# USB_DV_Stick_1V1_Sheet3.net
KiCad netlist of a schematic drawn in Altium Designer
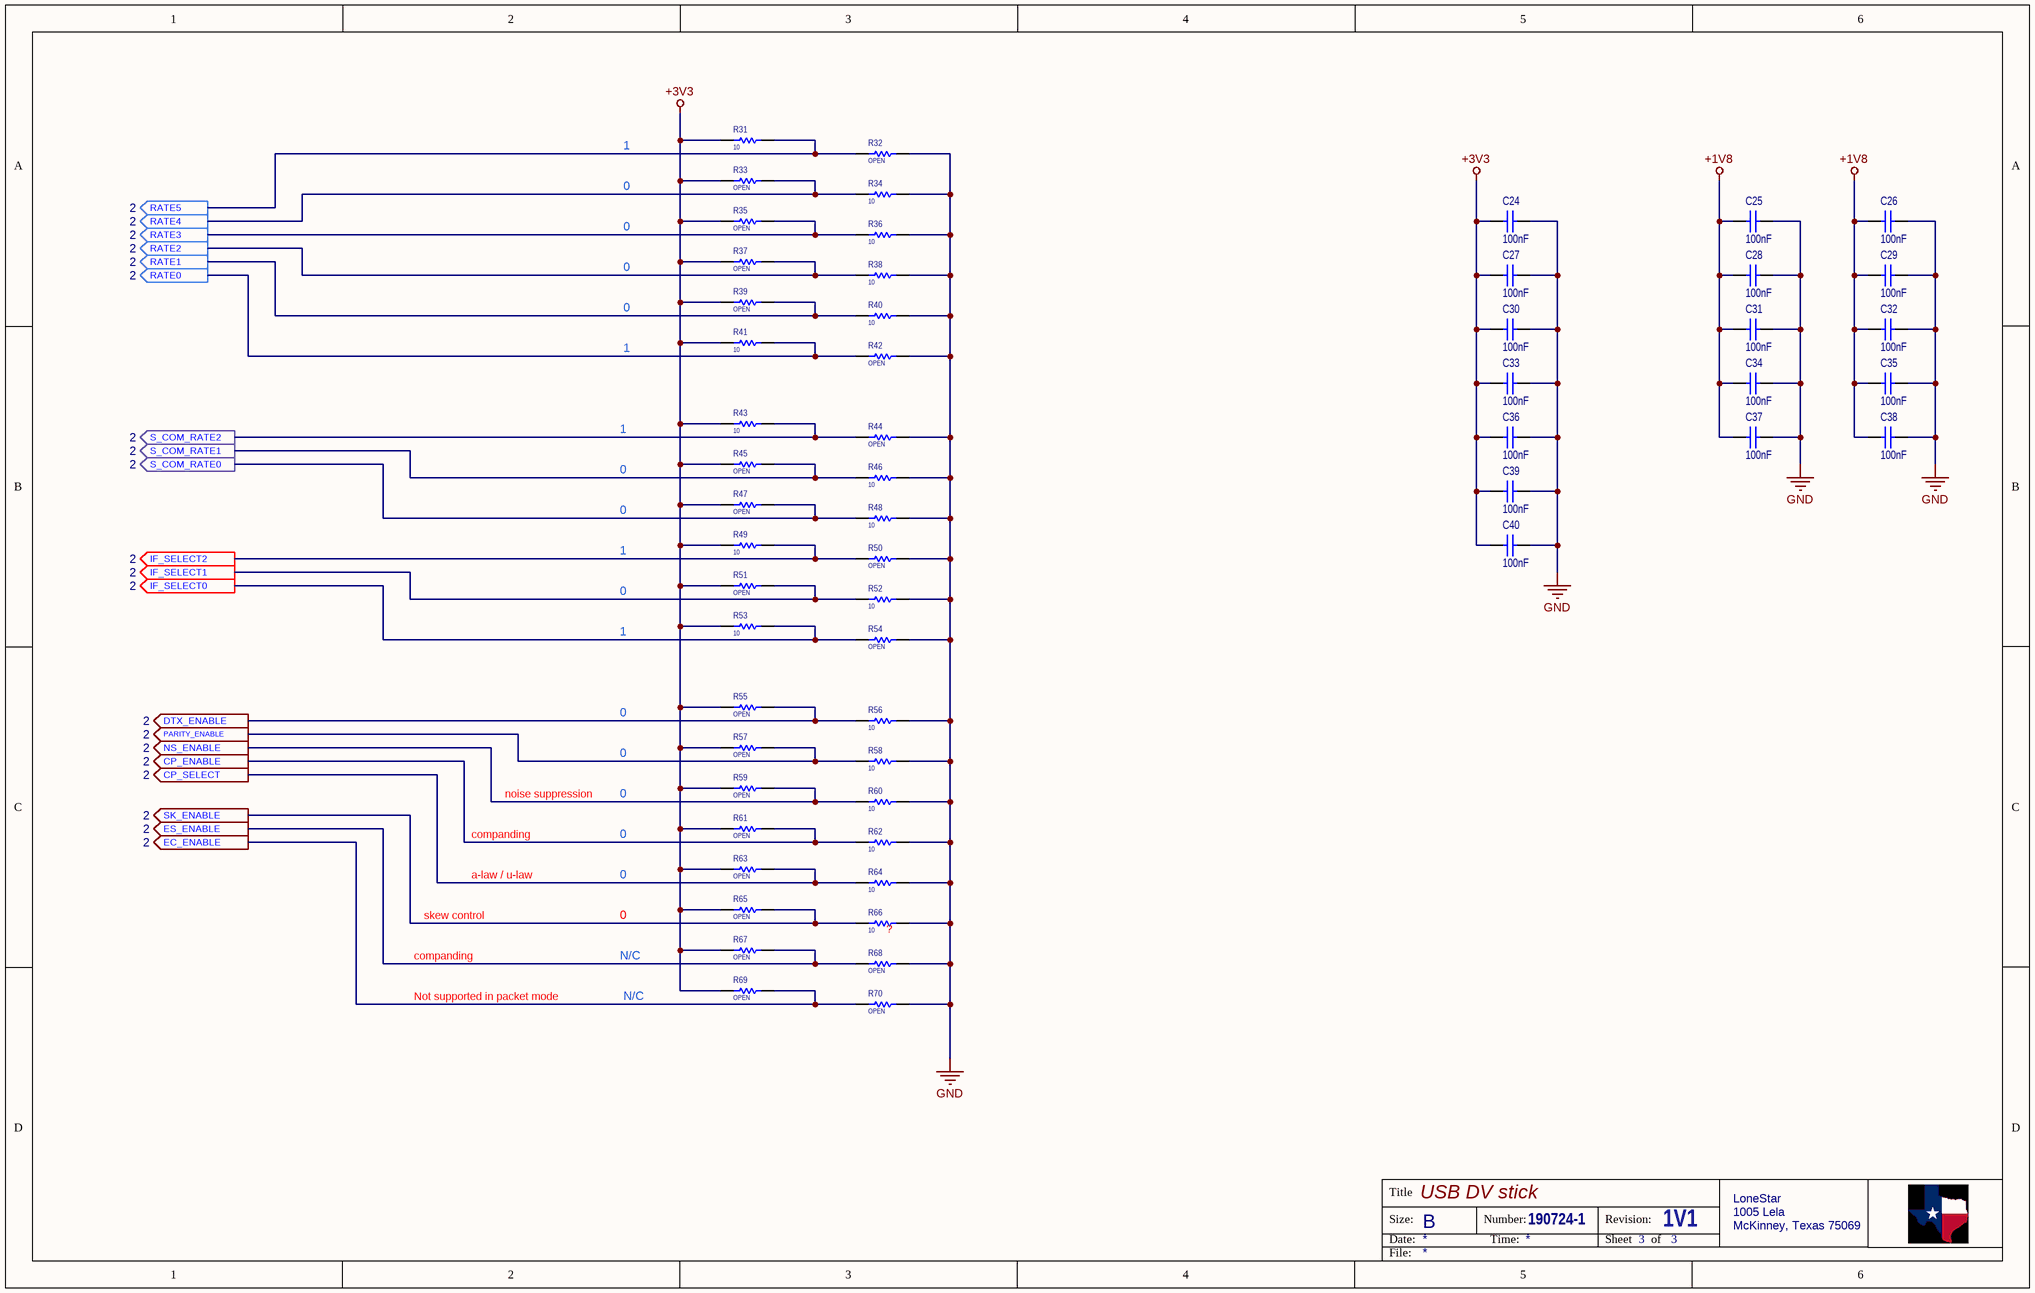
[diagram p0: USB DV Stick 1V1_Sheet3.SchDoc]

(export (version "E")
  (design (tool "Eeschema 10.0.6"))
  (components
    (comp (ref "C24")
      (value "100nF")
      (footprint "C0402")
      (description "Capacitor Surface Mount")
      (fields
        (field (name "MANUFACTURER") "Murata Electronics")
        (field (name "MANUFACTURER PART NUMBER") "GRM155R61H104KE19D")
      )
      (libsource (lib "Dave's") (part "Cap SM"))
    )
    (comp (ref "C25")
      (value "100nF")
      (footprint "C0402")
      (description "Capacitor Surface Mount")
      (fields
        (field (name "MANUFACTURER") "Murata Electronics")
        (field (name "MANUFACTURER PART NUMBER") "GRM155R61H104KE19D")
      )
      (libsource (lib "Dave's") (part "Cap SM"))
    )
    (comp (ref "C26")
      (value "100nF")
      (footprint "C0402")
      (description "Capacitor Surface Mount")
      (fields
        (field (name "MANUFACTURER") "Murata Electronics")
        (field (name "MANUFACTURER PART NUMBER") "GRM155R61H104KE19D")
      )
      (libsource (lib "Dave's") (part "Cap SM"))
    )
    (comp (ref "C27")
      (value "100nF")
      (footprint "C0402")
      (description "Capacitor Surface Mount")
      (fields
        (field (name "MANUFACTURER") "Murata Electronics")
        (field (name "MANUFACTURER PART NUMBER") "GRM155R61H104KE19D")
      )
      (libsource (lib "Dave's") (part "Cap SM"))
    )
    (comp (ref "C28")
      (value "100nF")
      (footprint "C0402")
      (description "Capacitor Surface Mount")
      (fields
        (field (name "MANUFACTURER") "Murata Electronics")
        (field (name "MANUFACTURER PART NUMBER") "GRM155R61H104KE19D")
      )
      (libsource (lib "Dave's") (part "Cap SM"))
    )
    (comp (ref "C29")
      (value "100nF")
      (footprint "C0402")
      (description "Capacitor Surface Mount")
      (fields
        (field (name "MANUFACTURER") "Murata Electronics")
        (field (name "MANUFACTURER PART NUMBER") "GRM155R61H104KE19D")
      )
      (libsource (lib "Dave's") (part "Cap SM"))
    )
    (comp (ref "C30")
      (value "100nF")
      (footprint "C0402")
      (description "Capacitor Surface Mount")
      (fields
        (field (name "MANUFACTURER") "Murata Electronics")
        (field (name "MANUFACTURER PART NUMBER") "GRM155R61H104KE19D")
      )
      (libsource (lib "Dave's") (part "Cap SM"))
    )
    (comp (ref "C31")
      (value "100nF")
      (footprint "C0402")
      (description "Capacitor Surface Mount")
      (fields
        (field (name "MANUFACTURER") "Murata Electronics")
        (field (name "MANUFACTURER PART NUMBER") "GRM155R61H104KE19D")
      )
      (libsource (lib "Dave's") (part "Cap SM"))
    )
    (comp (ref "C32")
      (value "100nF")
      (footprint "C0402")
      (description "Capacitor Surface Mount")
      (fields
        (field (name "MANUFACTURER") "Murata Electronics")
        (field (name "MANUFACTURER PART NUMBER") "GRM155R61H104KE19D")
      )
      (libsource (lib "Dave's") (part "Cap SM"))
    )
    (comp (ref "C33")
      (value "100nF")
      (footprint "C0402")
      (description "Capacitor Surface Mount")
      (fields
        (field (name "MANUFACTURER") "Murata Electronics")
        (field (name "MANUFACTURER PART NUMBER") "GRM155R61H104KE19D")
      )
      (libsource (lib "Dave's") (part "Cap SM"))
    )
    (comp (ref "C34")
      (value "100nF")
      (footprint "C0402")
      (description "Capacitor Surface Mount")
      (fields
        (field (name "MANUFACTURER") "Murata Electronics")
        (field (name "MANUFACTURER PART NUMBER") "GRM155R61H104KE19D")
      )
      (libsource (lib "Dave's") (part "Cap SM"))
    )
    (comp (ref "C35")
      (value "100nF")
      (footprint "C0402")
      (description "Capacitor Surface Mount")
      (fields
        (field (name "MANUFACTURER") "Murata Electronics")
        (field (name "MANUFACTURER PART NUMBER") "GRM155R61H104KE19D")
      )
      (libsource (lib "Dave's") (part "Cap SM"))
    )
    (comp (ref "C36")
      (value "100nF")
      (footprint "C0402")
      (description "Capacitor Surface Mount")
      (fields
        (field (name "MANUFACTURER") "Murata Electronics")
        (field (name "MANUFACTURER PART NUMBER") "GRM155R61H104KE19D")
      )
      (libsource (lib "Dave's") (part "Cap SM"))
    )
    (comp (ref "C37")
      (value "100nF")
      (footprint "C0402")
      (description "Capacitor Surface Mount")
      (fields
        (field (name "MANUFACTURER") "Murata Electronics")
        (field (name "MANUFACTURER PART NUMBER") "GRM155R61H104KE19D")
      )
      (libsource (lib "Dave's") (part "Cap SM"))
    )
    (comp (ref "C38")
      (value "100nF")
      (footprint "C0402")
      (description "Capacitor Surface Mount")
      (fields
        (field (name "MANUFACTURER") "Murata Electronics")
        (field (name "MANUFACTURER PART NUMBER") "GRM155R61H104KE19D")
      )
      (libsource (lib "Dave's") (part "Cap SM"))
    )
    (comp (ref "C39")
      (value "100nF")
      (footprint "C0402")
      (description "Capacitor Surface Mount")
      (fields
        (field (name "MANUFACTURER") "Murata Electronics")
        (field (name "MANUFACTURER PART NUMBER") "GRM155R61H104KE19D")
      )
      (libsource (lib "Dave's") (part "Cap SM"))
    )
    (comp (ref "C40")
      (value "100nF")
      (footprint "C0402")
      (description "Capacitor Surface Mount")
      (fields
        (field (name "MANUFACTURER") "Murata Electronics")
        (field (name "MANUFACTURER PART NUMBER") "GRM155R61H104KE19D")
      )
      (libsource (lib "Dave's") (part "Cap SM"))
    )
    (comp (ref "R31")
      (value "10")
      (footprint "R0603")
      (description "Resistor Surface Mount")
      (fields
        (field (name "MANUFACTURER") "Vishay / Dale")
        (field (name "MANUFACTURER PART NUMBER") "CRCW060310R0FKEAC")
      )
      (libsource (lib "Dave's") (part "RES SM"))
    )
    (comp (ref "R32")
      (value "OPEN")
      (footprint "R0603")
      (description "Resistor Surface Mount")
      (libsource (lib "Dave's") (part "RES SM"))
    )
    (comp (ref "R33")
      (value "OPEN")
      (footprint "R0603")
      (description "Resistor Surface Mount")
      (libsource (lib "Dave's") (part "RES SM"))
    )
    (comp (ref "R34")
      (value "10")
      (footprint "R0603")
      (description "Resistor Surface Mount")
      (fields
        (field (name "MANUFACTURER") "Vishay / Dale")
        (field (name "MANUFACTURER PART NUMBER") "CRCW060310R0FKEAC")
      )
      (libsource (lib "Dave's") (part "RES SM"))
    )
    (comp (ref "R35")
      (value "OPEN")
      (footprint "R0603")
      (description "Resistor Surface Mount")
      (libsource (lib "Dave's") (part "RES SM"))
    )
    (comp (ref "R36")
      (value "10")
      (footprint "R0603")
      (description "Resistor Surface Mount")
      (fields
        (field (name "MANUFACTURER") "Vishay / Dale")
        (field (name "MANUFACTURER PART NUMBER") "CRCW060310R0FKEAC")
      )
      (libsource (lib "Dave's") (part "RES SM"))
    )
    (comp (ref "R37")
      (value "OPEN")
      (footprint "R0603")
      (description "Resistor Surface Mount")
      (libsource (lib "Dave's") (part "RES SM"))
    )
    (comp (ref "R38")
      (value "10")
      (footprint "R0603")
      (description "Resistor Surface Mount")
      (fields
        (field (name "MANUFACTURER") "Vishay / Dale")
        (field (name "MANUFACTURER PART NUMBER") "CRCW060310R0FKEAC")
      )
      (libsource (lib "Dave's") (part "RES SM"))
    )
    (comp (ref "R39")
      (value "OPEN")
      (footprint "R0603")
      (description "Resistor Surface Mount")
      (libsource (lib "Dave's") (part "RES SM"))
    )
    (comp (ref "R40")
      (value "10")
      (footprint "R0603")
      (description "Resistor Surface Mount")
      (fields
        (field (name "MANUFACTURER") "Vishay / Dale")
        (field (name "MANUFACTURER PART NUMBER") "CRCW060310R0FKEAC")
      )
      (libsource (lib "Dave's") (part "RES SM"))
    )
    (comp (ref "R41")
      (value "10")
      (footprint "R0603")
      (description "Resistor Surface Mount")
      (fields
        (field (name "MANUFACTURER") "Vishay / Dale")
        (field (name "MANUFACTURER PART NUMBER") "CRCW060310R0FKEAC")
      )
      (libsource (lib "Dave's") (part "RES SM"))
    )
    (comp (ref "R42")
      (value "OPEN")
      (footprint "R0603")
      (description "Resistor Surface Mount")
      (libsource (lib "Dave's") (part "RES SM"))
    )
    (comp (ref "R43")
      (value "10")
      (footprint "R0603")
      (description "Resistor Surface Mount")
      (fields
        (field (name "MANUFACTURER") "Vishay / Dale")
        (field (name "MANUFACTURER PART NUMBER") "CRCW060310R0FKEAC")
      )
      (libsource (lib "Dave's") (part "RES SM"))
    )
    (comp (ref "R44")
      (value "OPEN")
      (footprint "R0603")
      (description "Resistor Surface Mount")
      (libsource (lib "Dave's") (part "RES SM"))
    )
    (comp (ref "R45")
      (value "OPEN")
      (footprint "R0603")
      (description "Resistor Surface Mount")
      (libsource (lib "Dave's") (part "RES SM"))
    )
    (comp (ref "R46")
      (value "10")
      (footprint "R0603")
      (description "Resistor Surface Mount")
      (fields
        (field (name "MANUFACTURER") "Vishay / Dale")
        (field (name "MANUFACTURER PART NUMBER") "CRCW060310R0FKEAC")
      )
      (libsource (lib "Dave's") (part "RES SM"))
    )
    (comp (ref "R47")
      (value "OPEN")
      (footprint "R0603")
      (description "Resistor Surface Mount")
      (libsource (lib "Dave's") (part "RES SM"))
    )
    (comp (ref "R48")
      (value "10")
      (footprint "R0603")
      (description "Resistor Surface Mount")
      (fields
        (field (name "MANUFACTURER") "Vishay / Dale")
        (field (name "MANUFACTURER PART NUMBER") "CRCW060310R0FKEAC")
      )
      (libsource (lib "Dave's") (part "RES SM"))
    )
    (comp (ref "R49")
      (value "10")
      (footprint "R0603")
      (description "Resistor Surface Mount")
      (fields
        (field (name "MANUFACTURER") "Vishay / Dale")
        (field (name "MANUFACTURER PART NUMBER") "CRCW060310R0FKEAC")
      )
      (libsource (lib "Dave's") (part "RES SM"))
    )
    (comp (ref "R50")
      (value "OPEN")
      (footprint "R0603")
      (description "Resistor Surface Mount")
      (libsource (lib "Dave's") (part "RES SM"))
    )
    (comp (ref "R51")
      (value "OPEN")
      (footprint "R0603")
      (description "Resistor Surface Mount")
      (libsource (lib "Dave's") (part "RES SM"))
    )
    (comp (ref "R52")
      (value "10")
      (footprint "R0603")
      (description "Resistor Surface Mount")
      (fields
        (field (name "MANUFACTURER") "Vishay / Dale")
        (field (name "MANUFACTURER PART NUMBER") "CRCW060310R0FKEAC")
      )
      (libsource (lib "Dave's") (part "RES SM"))
    )
    (comp (ref "R53")
      (value "10")
      (footprint "R0603")
      (description "Resistor Surface Mount")
      (fields
        (field (name "MANUFACTURER") "Vishay / Dale")
        (field (name "MANUFACTURER PART NUMBER") "CRCW060310R0FKEAC")
      )
      (libsource (lib "Dave's") (part "RES SM"))
    )
    (comp (ref "R54")
      (value "OPEN")
      (footprint "R0603")
      (description "Resistor Surface Mount")
      (libsource (lib "Dave's") (part "RES SM"))
    )
    (comp (ref "R55")
      (value "OPEN")
      (footprint "R0603")
      (description "Resistor Surface Mount")
      (libsource (lib "Dave's") (part "RES SM"))
    )
    (comp (ref "R56")
      (value "10")
      (footprint "R0603")
      (description "Resistor Surface Mount")
      (fields
        (field (name "MANUFACTURER") "Vishay / Dale")
        (field (name "MANUFACTURER PART NUMBER") "CRCW060310R0FKEAC")
      )
      (libsource (lib "Dave's") (part "RES SM"))
    )
    (comp (ref "R57")
      (value "OPEN")
      (footprint "R0603")
      (description "Resistor Surface Mount")
      (libsource (lib "Dave's") (part "RES SM"))
    )
    (comp (ref "R58")
      (value "10")
      (footprint "R0603")
      (description "Resistor Surface Mount")
      (fields
        (field (name "MANUFACTURER") "Vishay / Dale")
        (field (name "MANUFACTURER PART NUMBER") "CRCW060310R0FKEAC")
      )
      (libsource (lib "Dave's") (part "RES SM"))
    )
    (comp (ref "R59")
      (value "OPEN")
      (footprint "R0603")
      (description "Resistor Surface Mount")
      (libsource (lib "Dave's") (part "RES SM"))
    )
    (comp (ref "R60")
      (value "10")
      (footprint "R0603")
      (description "Resistor Surface Mount")
      (fields
        (field (name "MANUFACTURER") "Vishay / Dale")
        (field (name "MANUFACTURER PART NUMBER") "CRCW060310R0FKEAC")
      )
      (libsource (lib "Dave's") (part "RES SM"))
    )
    (comp (ref "R61")
      (value "OPEN")
      (footprint "R0603")
      (description "Resistor Surface Mount")
      (libsource (lib "Dave's") (part "RES SM"))
    )
    (comp (ref "R62")
      (value "10")
      (footprint "R0603")
      (description "Resistor Surface Mount")
      (fields
        (field (name "MANUFACTURER") "Vishay / Dale")
        (field (name "MANUFACTURER PART NUMBER") "CRCW060310R0FKEAC")
      )
      (libsource (lib "Dave's") (part "RES SM"))
    )
    (comp (ref "R63")
      (value "OPEN")
      (footprint "R0603")
      (description "Resistor Surface Mount")
      (libsource (lib "Dave's") (part "RES SM"))
    )
    (comp (ref "R64")
      (value "10")
      (footprint "R0603")
      (description "Resistor Surface Mount")
      (fields
        (field (name "MANUFACTURER") "Vishay / Dale")
        (field (name "MANUFACTURER PART NUMBER") "CRCW060310R0FKEAC")
      )
      (libsource (lib "Dave's") (part "RES SM"))
    )
    (comp (ref "R65")
      (value "OPEN")
      (footprint "R0603")
      (description "Resistor Surface Mount")
      (libsource (lib "Dave's") (part "RES SM"))
    )
    (comp (ref "R66")
      (value "10")
      (footprint "R0603")
      (description "Resistor Surface Mount")
      (fields
        (field (name "MANUFACTURER") "Vishay / Dale")
        (field (name "MANUFACTURER PART NUMBER") "CRCW060310R0FKEAC")
      )
      (libsource (lib "Dave's") (part "RES SM"))
    )
    (comp (ref "R67")
      (value "OPEN")
      (footprint "R0603")
      (description "Resistor Surface Mount")
      (libsource (lib "Dave's") (part "RES SM"))
    )
    (comp (ref "R68")
      (value "OPEN")
      (footprint "R0603")
      (description "Resistor Surface Mount")
      (libsource (lib "Dave's") (part "RES SM"))
    )
    (comp (ref "R69")
      (value "OPEN")
      (footprint "R0603")
      (description "Resistor Surface Mount")
      (libsource (lib "Dave's") (part "RES SM"))
    )
    (comp (ref "R70")
      (value "OPEN")
      (footprint "R0603")
      (description "Resistor Surface Mount")
      (libsource (lib "Dave's") (part "RES SM"))
    )
  )
  (nets
    (net (code "1") (name "+1V8") (class "Default")
      (node (ref "C25") (pin "1") (pinfunction "1_1") (pintype "passive"))
      (node (ref "C26") (pin "1") (pinfunction "1_1") (pintype "passive"))
      (node (ref "C28") (pin "1") (pinfunction "1_1") (pintype "passive"))
      (node (ref "C29") (pin "1") (pinfunction "1_1") (pintype "passive"))
      (node (ref "C31") (pin "1") (pinfunction "1_1") (pintype "passive"))
      (node (ref "C32") (pin "1") (pinfunction "1_1") (pintype "passive"))
      (node (ref "C34") (pin "1") (pinfunction "1_1") (pintype "passive"))
      (node (ref "C35") (pin "1") (pinfunction "1_1") (pintype "passive"))
      (node (ref "C37") (pin "1") (pinfunction "1_1") (pintype "passive"))
      (node (ref "C38") (pin "1") (pinfunction "1_1") (pintype "passive"))
    )
    (net (code "2") (name "+3V3") (class "Default")
      (node (ref "C24") (pin "1") (pinfunction "1_1") (pintype "passive"))
      (node (ref "C27") (pin "1") (pinfunction "1_1") (pintype "passive"))
      (node (ref "C30") (pin "1") (pinfunction "1_1") (pintype "passive"))
      (node (ref "C33") (pin "1") (pinfunction "1_1") (pintype "passive"))
      (node (ref "C36") (pin "1") (pinfunction "1_1") (pintype "passive"))
      (node (ref "C39") (pin "1") (pinfunction "1_1") (pintype "passive"))
      (node (ref "C40") (pin "1") (pinfunction "1_1") (pintype "passive"))
      (node (ref "R31") (pin "1") (pinfunction "1_1") (pintype "passive"))
      (node (ref "R33") (pin "1") (pinfunction "1_1") (pintype "passive"))
      (node (ref "R35") (pin "1") (pinfunction "1_1") (pintype "passive"))
      (node (ref "R37") (pin "1") (pinfunction "1_1") (pintype "passive"))
      (node (ref "R39") (pin "1") (pinfunction "1_1") (pintype "passive"))
      (node (ref "R41") (pin "1") (pinfunction "1_1") (pintype "passive"))
      (node (ref "R43") (pin "1") (pinfunction "1_1") (pintype "passive"))
      (node (ref "R45") (pin "1") (pinfunction "1_1") (pintype "passive"))
      (node (ref "R47") (pin "1") (pinfunction "1_1") (pintype "passive"))
      (node (ref "R49") (pin "1") (pinfunction "1_1") (pintype "passive"))
      (node (ref "R51") (pin "1") (pinfunction "1_1") (pintype "passive"))
      (node (ref "R53") (pin "1") (pinfunction "1_1") (pintype "passive"))
      (node (ref "R55") (pin "1") (pinfunction "1_1") (pintype "passive"))
      (node (ref "R57") (pin "1") (pinfunction "1_1") (pintype "passive"))
      (node (ref "R59") (pin "1") (pinfunction "1_1") (pintype "passive"))
      (node (ref "R61") (pin "1") (pinfunction "1_1") (pintype "passive"))
      (node (ref "R63") (pin "1") (pinfunction "1_1") (pintype "passive"))
      (node (ref "R65") (pin "1") (pinfunction "1_1") (pintype "passive"))
      (node (ref "R67") (pin "1") (pinfunction "1_1") (pintype "passive"))
      (node (ref "R69") (pin "1") (pinfunction "1_1") (pintype "passive"))
    )
    (net (code "3") (name "/CP_ENABLE") (class "Default")
      (node (ref "R61") (pin "2") (pinfunction "2_2") (pintype "passive"))
      (node (ref "R62") (pin "1") (pinfunction "1_1") (pintype "passive"))
    )
    (net (code "4") (name "/CP_SELECT") (class "Default")
      (node (ref "R63") (pin "2") (pinfunction "2_2") (pintype "passive"))
      (node (ref "R64") (pin "1") (pinfunction "1_1") (pintype "passive"))
    )
    (net (code "5") (name "/DTX_ENABLE") (class "Default")
      (node (ref "R55") (pin "2") (pinfunction "2_2") (pintype "passive"))
      (node (ref "R56") (pin "1") (pinfunction "1_1") (pintype "passive"))
    )
    (net (code "6") (name "/EC_ENABLE") (class "Default")
      (node (ref "R69") (pin "2") (pinfunction "2_2") (pintype "passive"))
      (node (ref "R70") (pin "1") (pinfunction "1_1") (pintype "passive"))
    )
    (net (code "7") (name "/ES_ENABLE") (class "Default")
      (node (ref "R67") (pin "2") (pinfunction "2_2") (pintype "passive"))
      (node (ref "R68") (pin "1") (pinfunction "1_1") (pintype "passive"))
    )
    (net (code "8") (name "/IF_SELECT0") (class "Default")
      (node (ref "R53") (pin "2") (pinfunction "2_2") (pintype "passive"))
      (node (ref "R54") (pin "1") (pinfunction "1_1") (pintype "passive"))
    )
    (net (code "9") (name "/IF_SELECT1") (class "Default")
      (node (ref "R51") (pin "2") (pinfunction "2_2") (pintype "passive"))
      (node (ref "R52") (pin "1") (pinfunction "1_1") (pintype "passive"))
    )
    (net (code "10") (name "/IF_SELECT2") (class "Default")
      (node (ref "R49") (pin "2") (pinfunction "2_2") (pintype "passive"))
      (node (ref "R50") (pin "1") (pinfunction "1_1") (pintype "passive"))
    )
    (net (code "11") (name "/NS_ENABLE") (class "Default")
      (node (ref "R59") (pin "2") (pinfunction "2_2") (pintype "passive"))
      (node (ref "R60") (pin "1") (pinfunction "1_1") (pintype "passive"))
    )
    (net (code "12") (name "/PARITY_ENABLE") (class "Default")
      (node (ref "R57") (pin "2") (pinfunction "2_2") (pintype "passive"))
      (node (ref "R58") (pin "1") (pinfunction "1_1") (pintype "passive"))
    )
    (net (code "13") (name "/RATE0") (class "Default")
      (node (ref "R41") (pin "2") (pinfunction "2_2") (pintype "passive"))
      (node (ref "R42") (pin "1") (pinfunction "1_1") (pintype "passive"))
    )
    (net (code "14") (name "/RATE1") (class "Default")
      (node (ref "R39") (pin "2") (pinfunction "2_2") (pintype "passive"))
      (node (ref "R40") (pin "1") (pinfunction "1_1") (pintype "passive"))
    )
    (net (code "15") (name "/RATE2") (class "Default")
      (node (ref "R37") (pin "2") (pinfunction "2_2") (pintype "passive"))
      (node (ref "R38") (pin "1") (pinfunction "1_1") (pintype "passive"))
    )
    (net (code "16") (name "/RATE3") (class "Default")
      (node (ref "R35") (pin "2") (pinfunction "2_2") (pintype "passive"))
      (node (ref "R36") (pin "1") (pinfunction "1_1") (pintype "passive"))
    )
    (net (code "17") (name "/RATE4") (class "Default")
      (node (ref "R33") (pin "2") (pinfunction "2_2") (pintype "passive"))
      (node (ref "R34") (pin "1") (pinfunction "1_1") (pintype "passive"))
    )
    (net (code "18") (name "/RATE5") (class "Default")
      (node (ref "R31") (pin "2") (pinfunction "2_2") (pintype "passive"))
      (node (ref "R32") (pin "1") (pinfunction "1_1") (pintype "passive"))
    )
    (net (code "19") (name "/SK_ENABLE") (class "Default")
      (node (ref "R65") (pin "2") (pinfunction "2_2") (pintype "passive"))
      (node (ref "R66") (pin "1") (pinfunction "1_1") (pintype "passive"))
    )
    (net (code "20") (name "/S_COM_RATE0") (class "Default")
      (node (ref "R47") (pin "2") (pinfunction "2_2") (pintype "passive"))
      (node (ref "R48") (pin "1") (pinfunction "1_1") (pintype "passive"))
    )
    (net (code "21") (name "/S_COM_RATE1") (class "Default")
      (node (ref "R45") (pin "2") (pinfunction "2_2") (pintype "passive"))
      (node (ref "R46") (pin "1") (pinfunction "1_1") (pintype "passive"))
    )
    (net (code "22") (name "/S_COM_RATE2") (class "Default")
      (node (ref "R43") (pin "2") (pinfunction "2_2") (pintype "passive"))
      (node (ref "R44") (pin "1") (pinfunction "1_1") (pintype "passive"))
    )
    (net (code "23") (name "GND") (class "Default")
      (node (ref "C24") (pin "2") (pinfunction "2_2") (pintype "passive"))
      (node (ref "C25") (pin "2") (pinfunction "2_2") (pintype "passive"))
      (node (ref "C26") (pin "2") (pinfunction "2_2") (pintype "passive"))
      (node (ref "C27") (pin "2") (pinfunction "2_2") (pintype "passive"))
      (node (ref "C28") (pin "2") (pinfunction "2_2") (pintype "passive"))
      (node (ref "C29") (pin "2") (pinfunction "2_2") (pintype "passive"))
      (node (ref "C30") (pin "2") (pinfunction "2_2") (pintype "passive"))
      (node (ref "C31") (pin "2") (pinfunction "2_2") (pintype "passive"))
      (node (ref "C32") (pin "2") (pinfunction "2_2") (pintype "passive"))
      (node (ref "C33") (pin "2") (pinfunction "2_2") (pintype "passive"))
      (node (ref "C34") (pin "2") (pinfunction "2_2") (pintype "passive"))
      (node (ref "C35") (pin "2") (pinfunction "2_2") (pintype "passive"))
      (node (ref "C36") (pin "2") (pinfunction "2_2") (pintype "passive"))
      (node (ref "C37") (pin "2") (pinfunction "2_2") (pintype "passive"))
      (node (ref "C38") (pin "2") (pinfunction "2_2") (pintype "passive"))
      (node (ref "C39") (pin "2") (pinfunction "2_2") (pintype "passive"))
      (node (ref "C40") (pin "2") (pinfunction "2_2") (pintype "passive"))
      (node (ref "R32") (pin "2") (pinfunction "2_2") (pintype "passive"))
      (node (ref "R34") (pin "2") (pinfunction "2_2") (pintype "passive"))
      (node (ref "R36") (pin "2") (pinfunction "2_2") (pintype "passive"))
      (node (ref "R38") (pin "2") (pinfunction "2_2") (pintype "passive"))
      (node (ref "R40") (pin "2") (pinfunction "2_2") (pintype "passive"))
      (node (ref "R42") (pin "2") (pinfunction "2_2") (pintype "passive"))
      (node (ref "R44") (pin "2") (pinfunction "2_2") (pintype "passive"))
      (node (ref "R46") (pin "2") (pinfunction "2_2") (pintype "passive"))
      (node (ref "R48") (pin "2") (pinfunction "2_2") (pintype "passive"))
      (node (ref "R50") (pin "2") (pinfunction "2_2") (pintype "passive"))
      (node (ref "R52") (pin "2") (pinfunction "2_2") (pintype "passive"))
      (node (ref "R54") (pin "2") (pinfunction "2_2") (pintype "passive"))
      (node (ref "R56") (pin "2") (pinfunction "2_2") (pintype "passive"))
      (node (ref "R58") (pin "2") (pinfunction "2_2") (pintype "passive"))
      (node (ref "R60") (pin "2") (pinfunction "2_2") (pintype "passive"))
      (node (ref "R62") (pin "2") (pinfunction "2_2") (pintype "passive"))
      (node (ref "R64") (pin "2") (pinfunction "2_2") (pintype "passive"))
      (node (ref "R66") (pin "2") (pinfunction "2_2") (pintype "passive"))
      (node (ref "R68") (pin "2") (pinfunction "2_2") (pintype "passive"))
      (node (ref "R70") (pin "2") (pinfunction "2_2") (pintype "passive"))
    )
  )
)
